# universky-MCU.net
KiCad netlist of a schematic drawn in Altium Designer
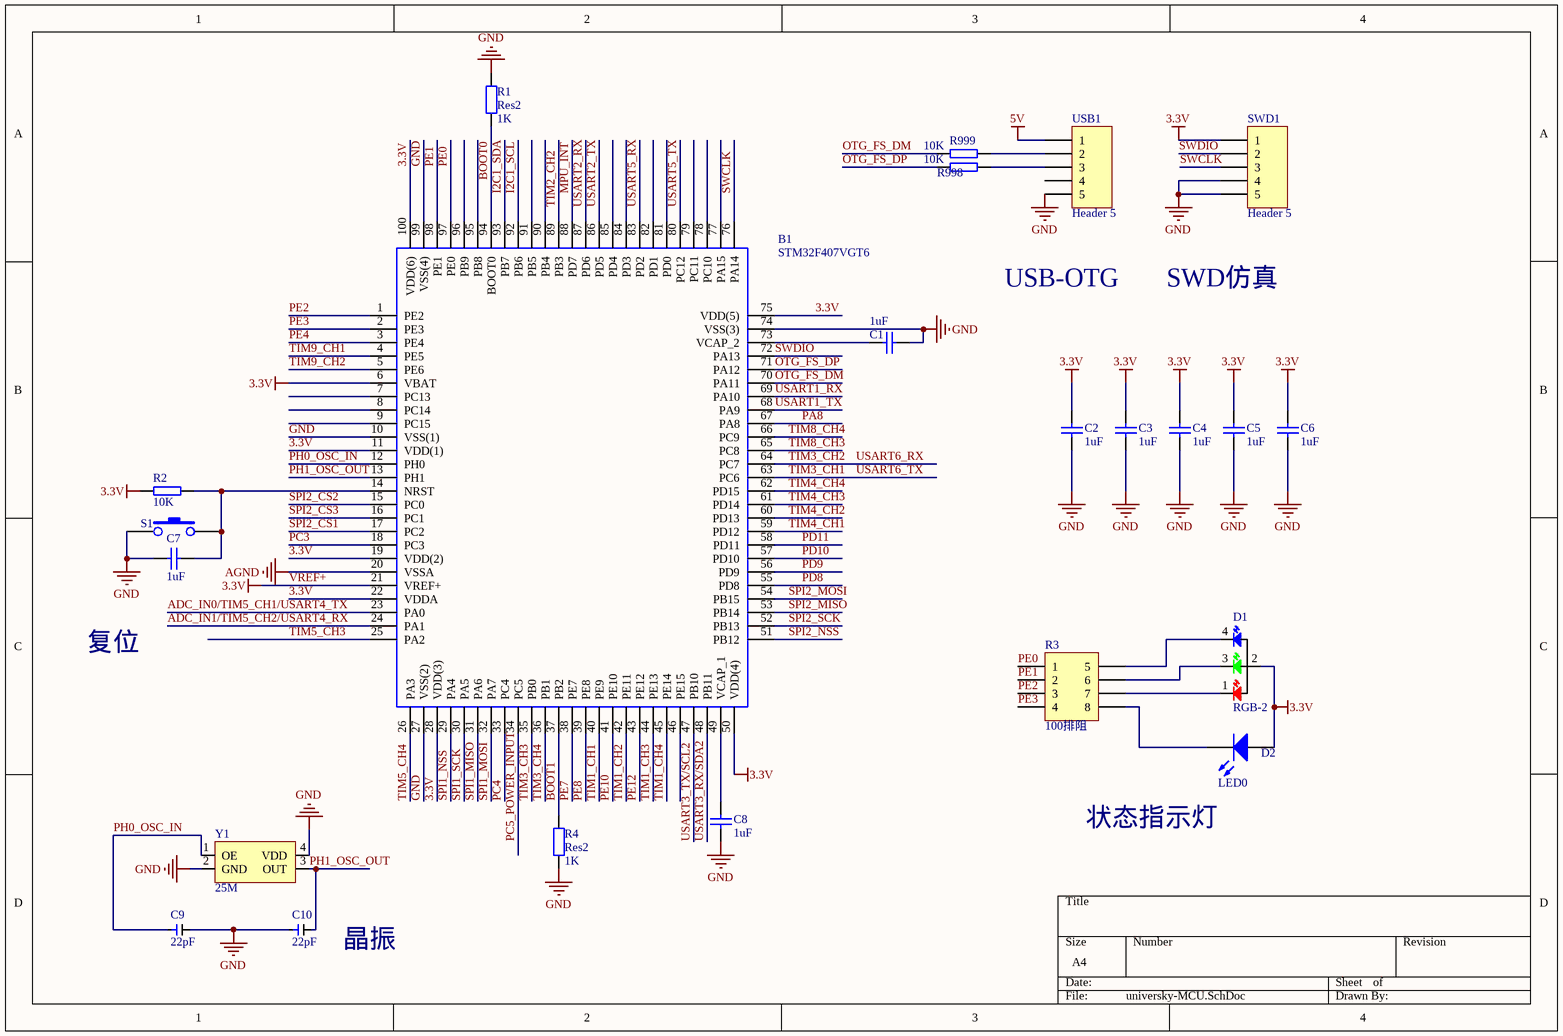
[diagram p0: universky-MCU.SchDoc]

(export (version "E")
  (design (tool "Eeschema 10.0.6"))
  (components
    (comp (ref "B1")
      (value "STM32F407VGT6")
      (footprint "QFP50P1600X1600X160-100N")
      (fields (field (name "RS PART NUMBER") "7468226"))
      (libsource (lib "universea") (part "STM32F407VGT6"))
    )
    (comp (ref "C1")
      (value "1uF")
      (footprint "0603_C")
      (description "Capacitor")
      (fields (field (name "Comment") "Cap") (field (name "PUBLISHER") "Altium Limited"))
      (libsource (lib "Miscellaneous Devices") (part "Cap"))
    )
    (comp (ref "C2")
      (value "1uF")
      (footprint "0603_C")
      (description "Capacitor")
      (fields (field (name "Comment") "Cap") (field (name "PUBLISHER") "Altium Limited"))
      (libsource (lib "Miscellaneous Devices") (part "Cap"))
    )
    (comp (ref "C3")
      (value "1uF")
      (footprint "0603_C")
      (description "Capacitor")
      (fields (field (name "Comment") "Cap") (field (name "PUBLISHER") "Altium Limited"))
      (libsource (lib "Miscellaneous Devices") (part "Cap"))
    )
    (comp (ref "C4")
      (value "1uF")
      (footprint "0603_C")
      (description "Capacitor")
      (fields (field (name "Comment") "Cap") (field (name "PUBLISHER") "Altium Limited"))
      (libsource (lib "Miscellaneous Devices") (part "Cap"))
    )
    (comp (ref "C5")
      (value "1uF")
      (footprint "0603_C")
      (description "Capacitor")
      (fields (field (name "Comment") "Cap") (field (name "PUBLISHER") "Altium Limited"))
      (libsource (lib "Miscellaneous Devices") (part "Cap"))
    )
    (comp (ref "C6")
      (value "1uF")
      (footprint "0603_C")
      (description "Capacitor")
      (fields (field (name "Comment") "Cap") (field (name "PUBLISHER") "Altium Limited"))
      (libsource (lib "Miscellaneous Devices") (part "Cap"))
    )
    (comp (ref "C7")
      (value "1uF")
      (footprint "0603_C")
      (description "Capacitor")
      (fields (field (name "Comment") "Cap") (field (name "PUBLISHER") "Altium Limited"))
      (libsource (lib "Miscellaneous Devices") (part "Cap"))
    )
    (comp (ref "C8")
      (value "1uF")
      (footprint "0603_C")
      (description "Capacitor")
      (fields (field (name "Comment") "Cap") (field (name "PUBLISHER") "Altium Limited"))
      (libsource (lib "Miscellaneous Devices") (part "Cap"))
    )
    (comp (ref "C9") (value "22pF") (footprint "0603_C") (libsource (lib "自己画的原理图库") (part "CAP")))
    (comp (ref "C10") (value "22pF") (footprint "0603_C") (libsource (lib "自己画的原理图库") (part "CAP")))
    (comp (ref "D1") (value "RGB-2") (footprint "RGB-2") (libsource (lib "dx原理图库") (part "RGB-2")))
    (comp (ref "D2")
      (value "LED0")
      (footprint "0603_LED")
      (description "Typical INFRARED GaAs LED")
      (fields (field (name "PUBLISHER") "Altium Limited"))
      (libsource (lib "Miscellaneous Devices") (part "LED0"))
    )
    (comp (ref "R1")
      (value "Res2")
      (footprint "0603_R")
      (description "Resistor")
      (fields (field (name "ALTIUM_VALUE") "1K") (field (name "PUBLISHER") "Altium Limited"))
      (libsource (lib "Miscellaneous Devices") (part "Res2"))
    )
    (comp (ref "R2")
      (value "RES_10K")
      (footprint "0603_R")
      (fields (field (name "ALTIUM_UNNAMED_1") "10K"))
      (libsource (lib "Flyking 常用元件") (part "RES_10K"))
    )
    (comp (ref "R3")
      (value "100排阻")
      (footprint "HDR_R_4")
      (description "Header, 4-Pin, Dual row")
      (fields (field (name "PUBLISHER") "Altium Limited"))
      (libsource (lib "Miscellaneous Connectors") (part "Header 4X2A"))
    )
    (comp (ref "R4")
      (value "Res2")
      (footprint "0603_R")
      (description "Resistor")
      (fields (field (name "ALTIUM_VALUE") "1K") (field (name "PUBLISHER") "Altium Limited"))
      (libsource (lib "Miscellaneous Devices") (part "Res2"))
    )
    (comp (ref "R998")
      (value "RES_10K")
      (footprint "0603_R")
      (fields (field (name "ALTIUM_UNNAMED_1") "10K"))
      (libsource (lib "Flyking 常用元件") (part "RES_10K"))
    )
    (comp (ref "R999")
      (value "RES_10K")
      (footprint "0603_R")
      (fields (field (name "ALTIUM_UNNAMED_1") "10K"))
      (libsource (lib "Flyking 常用元件") (part "RES_10K"))
    )
    (comp (ref "S1") (value "SW-PB") (footprint "KEY_SMD") (libsource (lib "SW开关") (part "SW-PB")))
    (comp (ref "SWD1")
      (value "Header 5")
      (footprint "USB_M")
      (description "Header, 5-Pin")
      (fields (field (name "PUBLISHER") "Altium Limited"))
      (libsource (lib "Miscellaneous Connectors") (part "Header 5"))
    )
    (comp (ref "USB1")
      (value "Header 5")
      (footprint "USB_M")
      (description "Header, 5-Pin")
      (fields (field (name "PUBLISHER") "Altium Limited"))
      (libsource (lib "Miscellaneous Connectors") (part "Header 5"))
    )
    (comp (ref "Y1")
      (value "25M")
      (footprint "XTAL_3225")
      (description "贴片有源晶振")
      (fields (field (name "Comment") "XATLS"))
      (libsource (lib "Fszhang") (part "XATLS"))
    )
  )
  (nets
    (net (code "1") (name "/ADC_IN0{slash}TIM5_CH1{slash}USART4_TX") (class "Default")
      (node (ref "B1") (pin "23") (pinfunction "PA0_23") (pintype "passive"))
    )
    (net (code "2") (name "/ADC_IN1{slash}TIM5_CH2{slash}USART4_RX") (class "Default")
      (node (ref "B1") (pin "24") (pinfunction "PA1_24") (pintype "passive"))
    )
    (net (code "3") (name "/BOOT0") (class "Default")
      (node (ref "B1") (pin "94") (pinfunction "BOOT0_94") (pintype "passive"))
      (node (ref "R1") (pin "1") (pinfunction "1_1") (pintype "passive"))
    )
    (net (code "4") (name "/BOOT1") (class "Default")
      (node (ref "B1") (pin "37") (pinfunction "PB2_37") (pintype "passive"))
      (node (ref "R4") (pin "2") (pinfunction "2_2") (pintype "passive"))
    )
    (net (code "5") (name "/I2C1_SCL") (class "Default")
      (node (ref "B1") (pin "92") (pinfunction "PB6_92") (pintype "passive"))
    )
    (net (code "6") (name "/I2C1_SDA") (class "Default")
      (node (ref "B1") (pin "93") (pinfunction "PB7_93") (pintype "passive"))
    )
    (net (code "7") (name "/MPU_INT") (class "Default")
      (node (ref "B1") (pin "88") (pinfunction "PD7_88") (pintype "passive"))
    )
    (net (code "8") (name "/OTG_FS_DM") (class "Default")
      (node (ref "B1") (pin "70") (pinfunction "PA11_70") (pintype "passive"))
      (node (ref "R999") (pin "2") (pintype "passive"))
    )
    (net (code "9") (name "/OTG_FS_DP") (class "Default")
      (node (ref "B1") (pin "71") (pinfunction "PA12_71") (pintype "passive"))
      (node (ref "R998") (pin "2") (pintype "passive"))
    )
    (net (code "10") (name "/PA8") (class "Default")
      (node (ref "B1") (pin "67") (pinfunction "PA8_67") (pintype "passive"))
    )
    (net (code "11") (name "/PC3") (class "Default")
      (node (ref "B1") (pin "18") (pinfunction "PC3_18") (pintype "passive"))
    )
    (net (code "12") (name "/PC4") (class "Default")
      (node (ref "B1") (pin "33") (pinfunction "PC4_33") (pintype "passive"))
    )
    (net (code "13") (name "/PC5_POWER_INPUT") (class "Default")
      (node (ref "B1") (pin "34") (pinfunction "PC5_34") (pintype "passive"))
    )
    (net (code "14") (name "/PD8") (class "Default")
      (node (ref "B1") (pin "55") (pinfunction "PD8_55") (pintype "passive"))
    )
    (net (code "15") (name "/PD9") (class "Default")
      (node (ref "B1") (pin "56") (pinfunction "PD9_56") (pintype "passive"))
    )
    (net (code "16") (name "/PD10") (class "Default")
      (node (ref "B1") (pin "57") (pinfunction "PD10_57") (pintype "passive"))
    )
    (net (code "17") (name "/PD11") (class "Default")
      (node (ref "B1") (pin "58") (pinfunction "PD11_58") (pintype "passive"))
    )
    (net (code "18") (name "/PE0") (class "Default")
      (node (ref "B1") (pin "97") (pinfunction "PE0_97") (pintype "passive"))
      (node (ref "R3") (pin "1") (pinfunction "1_1") (pintype "passive"))
    )
    (net (code "19") (name "/PE1") (class "Default")
      (node (ref "B1") (pin "98") (pinfunction "PE1_98") (pintype "passive"))
      (node (ref "R3") (pin "2") (pinfunction "2_2") (pintype "passive"))
    )
    (net (code "20") (name "/PE2") (class "Default")
      (node (ref "B1") (pin "1") (pinfunction "PE2_1") (pintype "passive"))
      (node (ref "R3") (pin "3") (pinfunction "3_3") (pintype "passive"))
    )
    (net (code "21") (name "/PE3") (class "Default")
      (node (ref "B1") (pin "2") (pinfunction "PE3_2") (pintype "passive"))
      (node (ref "R3") (pin "4") (pinfunction "4_4") (pintype "passive"))
    )
    (net (code "22") (name "/PE4") (class "Default")
      (node (ref "B1") (pin "3") (pinfunction "PE4_3") (pintype "passive"))
    )
    (net (code "23") (name "/PE7") (class "Default")
      (node (ref "B1") (pin "38") (pinfunction "PE7_38") (pintype "passive"))
    )
    (net (code "24") (name "/PE8") (class "Default")
      (node (ref "B1") (pin "39") (pinfunction "PE8_39") (pintype "passive"))
    )
    (net (code "25") (name "/PE10") (class "Default")
      (node (ref "B1") (pin "41") (pinfunction "PE10_41") (pintype "passive"))
    )
    (net (code "26") (name "/PE12") (class "Default")
      (node (ref "B1") (pin "43") (pinfunction "PE12_43") (pintype "passive"))
    )
    (net (code "27") (name "/PH0_OSC_IN") (class "Default")
      (node (ref "B1") (pin "12") (pinfunction "PH0_12") (pintype "passive"))
      (node (ref "C9") (pin "1") (pinfunction "1_1") (pintype "passive"))
      (node (ref "Y1") (pin "1") (pinfunction "OE_1") (pintype "passive"))
    )
    (net (code "28") (name "/PH1_OSC_OUT") (class "Default")
      (node (ref "B1") (pin "13") (pinfunction "PH1_13") (pintype "passive"))
      (node (ref "C10") (pin "2") (pinfunction "2_2") (pintype "passive"))
      (node (ref "Y1") (pin "3") (pinfunction "OUT_3") (pintype "passive"))
    )
    (net (code "29") (name "/SPI1_MISO") (class "Default")
      (node (ref "B1") (pin "31") (pinfunction "PA6_31") (pintype "passive"))
    )
    (net (code "30") (name "/SPI1_MOSI") (class "Default")
      (node (ref "B1") (pin "32") (pinfunction "PA7_32") (pintype "passive"))
    )
    (net (code "31") (name "/SPI1_NSS") (class "Default")
      (node (ref "B1") (pin "29") (pinfunction "PA4_29") (pintype "passive"))
    )
    (net (code "32") (name "/SPI1_SCK") (class "Default")
      (node (ref "B1") (pin "30") (pinfunction "PA5_30") (pintype "passive"))
    )
    (net (code "33") (name "/SPI2_CS1") (class "Default")
      (node (ref "B1") (pin "17") (pinfunction "PC2_17") (pintype "passive"))
    )
    (net (code "34") (name "/SPI2_CS2") (class "Default")
      (node (ref "B1") (pin "15") (pinfunction "PC0_15") (pintype "passive"))
    )
    (net (code "35") (name "/SPI2_CS3") (class "Default")
      (node (ref "B1") (pin "16") (pinfunction "PC1_16") (pintype "passive"))
    )
    (net (code "36") (name "/SPI2_MISO") (class "Default")
      (node (ref "B1") (pin "53") (pinfunction "PB14_53") (pintype "passive"))
    )
    (net (code "37") (name "/SPI2_MOSI") (class "Default")
      (node (ref "B1") (pin "54") (pinfunction "PB15_54") (pintype "passive"))
    )
    (net (code "38") (name "/SPI2_NSS") (class "Default")
      (node (ref "B1") (pin "51") (pinfunction "PB12_51") (pintype "passive"))
    )
    (net (code "39") (name "/SPI2_SCK") (class "Default")
      (node (ref "B1") (pin "52") (pinfunction "PB13_52") (pintype "passive"))
    )
    (net (code "40") (name "/SWCLK") (class "Default")
      (node (ref "B1") (pin "76") (pinfunction "PA14_76") (pintype "passive"))
      (node (ref "SWD1") (pin "3") (pinfunction "3_3") (pintype "passive"))
    )
    (net (code "41") (name "/SWDIO") (class "Default")
      (node (ref "B1") (pin "72") (pinfunction "PA13_72") (pintype "passive"))
      (node (ref "SWD1") (pin "2") (pinfunction "2_2") (pintype "passive"))
    )
    (net (code "42") (name "/TIM1_CH1") (class "Default")
      (node (ref "B1") (pin "40") (pinfunction "PE9_40") (pintype "passive"))
    )
    (net (code "43") (name "/TIM1_CH2") (class "Default")
      (node (ref "B1") (pin "42") (pinfunction "PE11_42") (pintype "passive"))
    )
    (net (code "44") (name "/TIM1_CH3") (class "Default")
      (node (ref "B1") (pin "44") (pinfunction "PE13_44") (pintype "passive"))
    )
    (net (code "45") (name "/TIM1_CH4") (class "Default")
      (node (ref "B1") (pin "45") (pinfunction "PE14_45") (pintype "passive"))
    )
    (net (code "46") (name "/TIM2_CH2") (class "Default")
      (node (ref "B1") (pin "89") (pinfunction "PB3_89") (pintype "passive"))
    )
    (net (code "47") (name "/TIM3_CH1") (class "Default")
      (node (ref "B1") (pin "63") (pinfunction "PC6_63") (pintype "passive"))
    )
    (net (code "48") (name "/TIM3_CH2") (class "Default")
      (node (ref "B1") (pin "64") (pinfunction "PC7_64") (pintype "passive"))
    )
    (net (code "49") (name "/TIM3_CH3") (class "Default")
      (node (ref "B1") (pin "35") (pinfunction "PB0_35") (pintype "passive"))
    )
    (net (code "50") (name "/TIM3_CH4") (class "Default")
      (node (ref "B1") (pin "36") (pinfunction "PB1_36") (pintype "passive"))
    )
    (net (code "51") (name "/TIM4_CH1") (class "Default")
      (node (ref "B1") (pin "59") (pinfunction "PD12_59") (pintype "passive"))
    )
    (net (code "52") (name "/TIM4_CH2") (class "Default")
      (node (ref "B1") (pin "60") (pinfunction "PD13_60") (pintype "passive"))
    )
    (net (code "53") (name "/TIM4_CH3") (class "Default")
      (node (ref "B1") (pin "61") (pinfunction "PD14_61") (pintype "passive"))
    )
    (net (code "54") (name "/TIM4_CH4") (class "Default")
      (node (ref "B1") (pin "62") (pinfunction "PD15_62") (pintype "passive"))
    )
    (net (code "55") (name "/TIM5_CH3") (class "Default")
      (node (ref "B1") (pin "25") (pinfunction "PA2_25") (pintype "passive"))
    )
    (net (code "56") (name "/TIM5_CH4") (class "Default")
      (node (ref "B1") (pin "26") (pinfunction "PA3_26") (pintype "passive"))
    )
    (net (code "57") (name "/TIM8_CH3") (class "Default")
      (node (ref "B1") (pin "65") (pinfunction "PC8_65") (pintype "passive"))
    )
    (net (code "58") (name "/TIM8_CH4") (class "Default")
      (node (ref "B1") (pin "66") (pinfunction "PC9_66") (pintype "passive"))
    )
    (net (code "59") (name "/TIM9_CH1") (class "Default")
      (node (ref "B1") (pin "4") (pinfunction "PE5_4") (pintype "passive"))
    )
    (net (code "60") (name "/TIM9_CH2") (class "Default")
      (node (ref "B1") (pin "5") (pinfunction "PE6_5") (pintype "passive"))
    )
    (net (code "61") (name "/USART1_RX") (class "Default")
      (node (ref "B1") (pin "69") (pinfunction "PA10_69") (pintype "passive"))
    )
    (net (code "62") (name "/USART1_TX") (class "Default")
      (node (ref "B1") (pin "68") (pinfunction "PA9_68") (pintype "passive"))
    )
    (net (code "63") (name "/USART2_RX") (class "Default")
      (node (ref "B1") (pin "87") (pinfunction "PD6_87") (pintype "passive"))
    )
    (net (code "64") (name "/USART2_TX") (class "Default")
      (node (ref "B1") (pin "86") (pinfunction "PD5_86") (pintype "passive"))
    )
    (net (code "65") (name "/USART3_RX{slash}SDA2") (class "Default")
      (node (ref "B1") (pin "48") (pinfunction "PB11_48") (pintype "passive"))
    )
    (net (code "66") (name "/USART3_TX{slash}SCL2") (class "Default")
      (node (ref "B1") (pin "47") (pinfunction "PB10_47") (pintype "passive"))
    )
    (net (code "67") (name "/USART5_RX") (class "Default")
      (node (ref "B1") (pin "83") (pinfunction "PD2_83") (pintype "passive"))
    )
    (net (code "68") (name "/USART5_TX") (class "Default")
      (node (ref "B1") (pin "80") (pinfunction "PC12_80") (pintype "passive"))
    )
    (net (code "69") (name "3.3V") (class "Default")
      (node (ref "B1") (pin "100") (pinfunction "VDD(6)_100") (pintype "power_in"))
      (node (ref "B1") (pin "11") (pinfunction "VDD(1)_11") (pintype "power_in"))
      (node (ref "B1") (pin "19") (pinfunction "VDD(2)_19") (pintype "power_in"))
      (node (ref "B1") (pin "21") (pinfunction "VREF+_21") (pintype "passive"))
      (node (ref "B1") (pin "22") (pinfunction "VDDA_22") (pintype "power_in"))
      (node (ref "B1") (pin "28") (pinfunction "VDD(3)_28") (pintype "power_in"))
      (node (ref "B1") (pin "50") (pinfunction "VDD(4)_50") (pintype "power_in"))
      (node (ref "B1") (pin "6") (pinfunction "VBAT_6") (pintype "passive"))
      (node (ref "B1") (pin "75") (pinfunction "VDD(5)_75") (pintype "power_in"))
      (node (ref "C2") (pin "2") (pinfunction "2_2") (pintype "passive"))
      (node (ref "C3") (pin "2") (pinfunction "2_2") (pintype "passive"))
      (node (ref "C4") (pin "2") (pinfunction "2_2") (pintype "passive"))
      (node (ref "C5") (pin "2") (pinfunction "2_2") (pintype "passive"))
      (node (ref "C6") (pin "2") (pinfunction "2_2") (pintype "passive"))
      (node (ref "D1") (pin "2") (pintype "passive"))
      (node (ref "D2") (pin "1") (pinfunction "A_1") (pintype "passive"))
      (node (ref "R2") (pin "2") (pintype "passive"))
      (node (ref "SWD1") (pin "1") (pinfunction "1_1") (pintype "passive"))
    )
    (net (code "70") (name "5V") (class "Default")
      (node (ref "USB1") (pin "1") (pinfunction "1_1") (pintype "passive"))
    )
    (net (code "71") (name "AGND") (class "Default")
      (node (ref "B1") (pin "20") (pinfunction "VSSA_20") (pintype "passive"))
    )
    (net (code "72") (name "GND") (class "Default")
      (node (ref "B1") (pin "10") (pinfunction "VSS(1)_10") (pintype "passive"))
      (node (ref "B1") (pin "27") (pinfunction "VSS(2)_27") (pintype "passive"))
      (node (ref "B1") (pin "74") (pinfunction "VSS(3)_74") (pintype "passive"))
      (node (ref "B1") (pin "99") (pinfunction "VSS(4)_99") (pintype "passive"))
      (node (ref "C1") (pin "2") (pinfunction "2_2") (pintype "passive"))
      (node (ref "C10") (pin "1") (pinfunction "1_1") (pintype "passive"))
      (node (ref "C2") (pin "1") (pinfunction "1_1") (pintype "passive"))
      (node (ref "C3") (pin "1") (pinfunction "1_1") (pintype "passive"))
      (node (ref "C4") (pin "1") (pinfunction "1_1") (pintype "passive"))
      (node (ref "C5") (pin "1") (pinfunction "1_1") (pintype "passive"))
      (node (ref "C6") (pin "1") (pinfunction "1_1") (pintype "passive"))
      (node (ref "C7") (pin "2") (pinfunction "2_2") (pintype "passive"))
      (node (ref "C8") (pin "1") (pinfunction "1_1") (pintype "passive"))
      (node (ref "C9") (pin "2") (pinfunction "2_2") (pintype "passive"))
      (node (ref "R1") (pin "2") (pinfunction "2_2") (pintype "passive"))
      (node (ref "R4") (pin "1") (pinfunction "1_1") (pintype "passive"))
      (node (ref "S1") (pin "1") (pinfunction "1_1") (pintype "passive"))
      (node (ref "SWD1") (pin "4") (pinfunction "4_4") (pintype "passive"))
      (node (ref "SWD1") (pin "5") (pinfunction "5_5") (pintype "passive"))
      (node (ref "USB1") (pin "5") (pinfunction "5_5") (pintype "passive"))
      (node (ref "Y1") (pin "2") (pinfunction "GND_2") (pintype "passive"))
      (node (ref "Y1") (pin "4") (pinfunction "VDD_4") (pintype "passive"))
    )
    (net (code "73") (name "Net-(B1-NRST)") (class "Default")
      (node (ref "B1") (pin "14") (pinfunction "NRST_14") (pintype "passive"))
      (node (ref "C7") (pin "1") (pinfunction "1_1") (pintype "passive"))
      (node (ref "R2") (pin "1") (pintype "passive"))
      (node (ref "S1") (pin "2") (pinfunction "2_2") (pintype "passive"))
    )
    (net (code "74") (name "Net-(B1-VCAP_1)") (class "Default")
      (node (ref "B1") (pin "49") (pinfunction "VCAP_1_49") (pintype "passive"))
      (node (ref "C8") (pin "2") (pinfunction "2_2") (pintype "passive"))
    )
    (net (code "75") (name "Net-(B1-VCAP_2)") (class "Default")
      (node (ref "B1") (pin "73") (pinfunction "VCAP_2_73") (pintype "passive"))
      (node (ref "C1") (pin "1") (pinfunction "1_1") (pintype "passive"))
    )
    (net (code "76") (name "Net-(D1-B)") (class "Default")
      (node (ref "D1") (pin "4") (pinfunction "B_4") (pintype "passive"))
      (node (ref "R3") (pin "5") (pinfunction "5_5") (pintype "passive"))
    )
    (net (code "77") (name "Net-(D1-G)") (class "Default")
      (node (ref "D1") (pin "3") (pinfunction "G_3") (pintype "passive"))
      (node (ref "R3") (pin "6") (pinfunction "6_6") (pintype "passive"))
    )
    (net (code "78") (name "Net-(D1-R)") (class "Default")
      (node (ref "D1") (pin "1") (pinfunction "R_1") (pintype "passive"))
      (node (ref "R3") (pin "7") (pinfunction "7_7") (pintype "passive"))
    )
    (net (code "79") (name "Net-(D2-K)") (class "Default")
      (node (ref "D2") (pin "2") (pinfunction "K_2") (pintype "passive"))
      (node (ref "R3") (pin "8") (pinfunction "8_8") (pintype "passive"))
    )
    (net (code "80") (name "Net-(R998-Pad1)") (class "Default")
      (node (ref "R998") (pin "1") (pintype "passive"))
      (node (ref "USB1") (pin "3") (pinfunction "3_3") (pintype "passive"))
    )
    (net (code "81") (name "Net-(R999-Pad1)") (class "Default")
      (node (ref "R999") (pin "1") (pintype "passive"))
      (node (ref "USB1") (pin "2") (pinfunction "2_2") (pintype "passive"))
    )
    (net (code "82") (name "unconnected-(B1-PA15-Pad77)") (class "Default")
      (node (ref "B1") (pin "77") (pinfunction "PA15_77") (pintype "passive"))
    )
    (net (code "83") (name "unconnected-(B1-PB4-Pad90)") (class "Default")
      (node (ref "B1") (pin "90") (pinfunction "PB4_90") (pintype "passive"))
    )
    (net (code "84") (name "unconnected-(B1-PB5-Pad91)") (class "Default")
      (node (ref "B1") (pin "91") (pinfunction "PB5_91") (pintype "passive"))
    )
    (net (code "85") (name "unconnected-(B1-PB8-Pad95)") (class "Default")
      (node (ref "B1") (pin "95") (pinfunction "PB8_95") (pintype "passive"))
    )
    (net (code "86") (name "unconnected-(B1-PB9-Pad96)") (class "Default")
      (node (ref "B1") (pin "96") (pinfunction "PB9_96") (pintype "passive"))
    )
    (net (code "87") (name "unconnected-(B1-PC10-Pad78)") (class "Default")
      (node (ref "B1") (pin "78") (pinfunction "PC10_78") (pintype "passive"))
    )
    (net (code "88") (name "unconnected-(B1-PC11-Pad79)") (class "Default")
      (node (ref "B1") (pin "79") (pinfunction "PC11_79") (pintype "passive"))
    )
    (net (code "89") (name "unconnected-(B1-PC13-Pad7)") (class "Default")
      (node (ref "B1") (pin "7") (pinfunction "PC13_7") (pintype "passive"))
    )
    (net (code "90") (name "unconnected-(B1-PC14-Pad8)") (class "Default")
      (node (ref "B1") (pin "8") (pinfunction "PC14_8") (pintype "passive"))
    )
    (net (code "91") (name "unconnected-(B1-PC15-Pad9)") (class "Default")
      (node (ref "B1") (pin "9") (pinfunction "PC15_9") (pintype "passive"))
    )
    (net (code "92") (name "unconnected-(B1-PD0-Pad81)") (class "Default")
      (node (ref "B1") (pin "81") (pinfunction "PD0_81") (pintype "passive"))
    )
    (net (code "93") (name "unconnected-(B1-PD1-Pad82)") (class "Default")
      (node (ref "B1") (pin "82") (pinfunction "PD1_82") (pintype "passive"))
    )
    (net (code "94") (name "unconnected-(B1-PD3-Pad84)") (class "Default")
      (node (ref "B1") (pin "84") (pinfunction "PD3_84") (pintype "passive"))
    )
    (net (code "95") (name "unconnected-(B1-PD4-Pad85)") (class "Default")
      (node (ref "B1") (pin "85") (pinfunction "PD4_85") (pintype "passive"))
    )
    (net (code "96") (name "unconnected-(B1-PE15-Pad46)") (class "Default")
      (node (ref "B1") (pin "46") (pinfunction "PE15_46") (pintype "passive"))
    )
    (net (code "97") (name "unconnected-(USB1-Pad4)") (class "Default")
      (node (ref "USB1") (pin "4") (pinfunction "4_4") (pintype "passive"))
    )
  )
)
